# ESP32_RF.net
KiCad netlist of a schematic drawn in Altium Designer
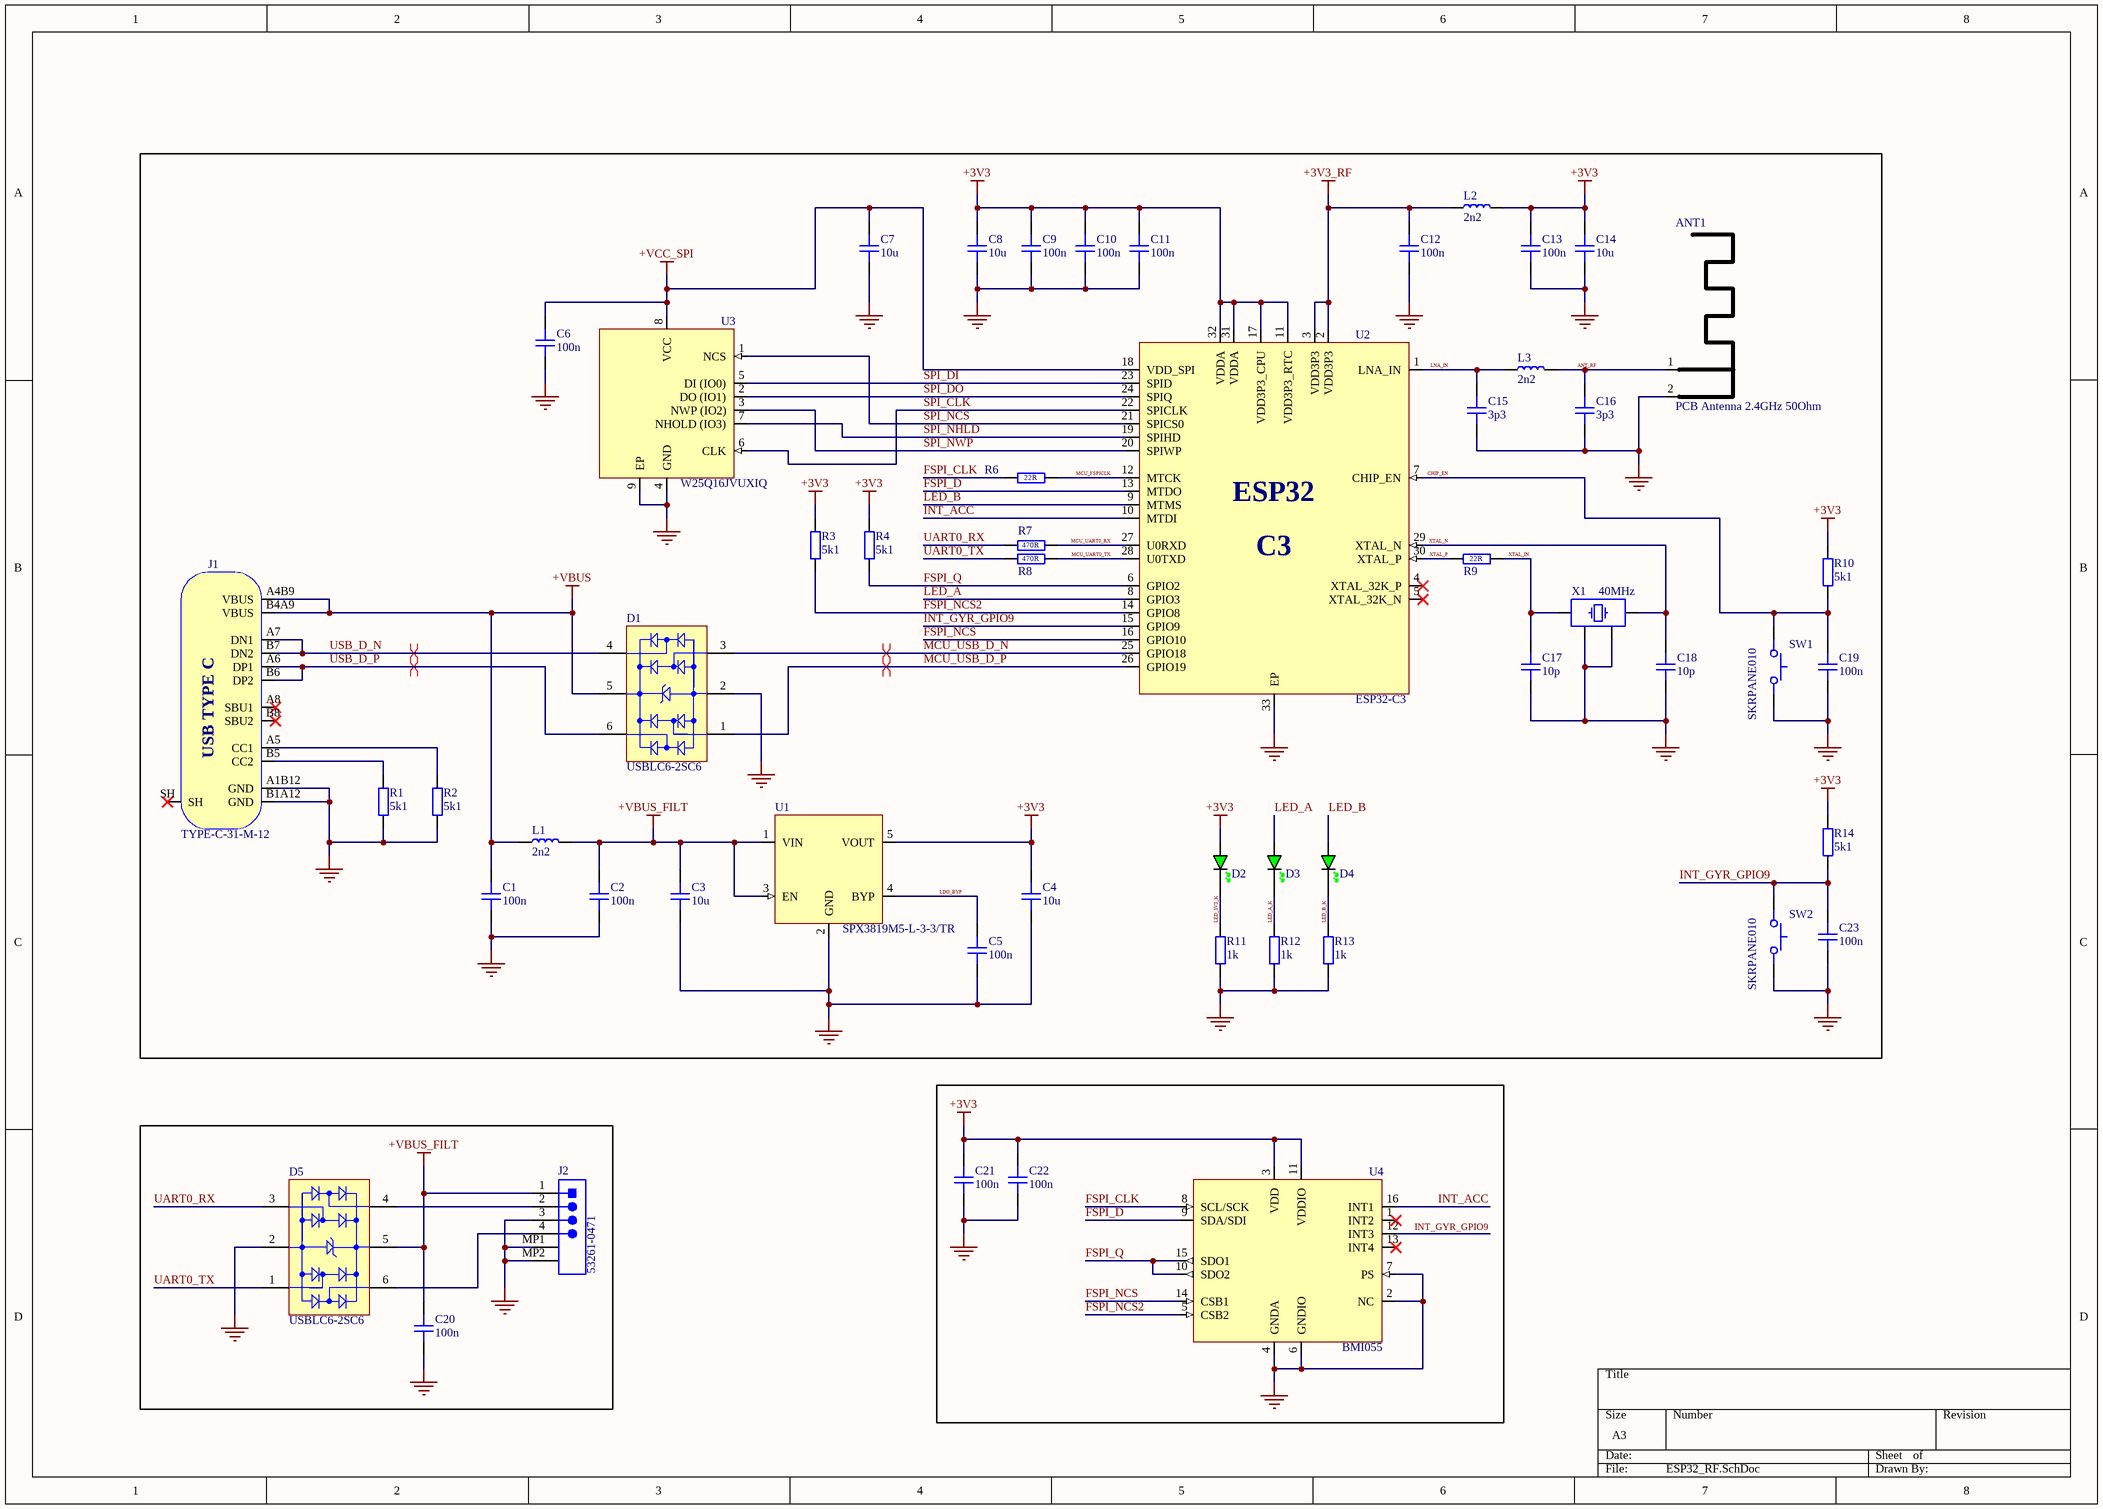
[diagram p0: ESP32_RF.SchDoc]

(export (version "E")
  (design (tool "Eeschema 10.0.6"))
  (components
    (comp (ref "ANT1")
      (value "PCB Antenna 2.4GHz 50Ohm")
      (footprint "ANT_IFA_USB_2_4GHZ_50R")
      (description "Inverted F 2.4GHz ISM PCB Antenna 50 Ohm")
      (libsource (lib "Schematic-Lib-PhilsLab") (part "ANT_IFA_USB_2_4GHZ_50R"))
    )
    (comp (ref "C1")
      (value "100n")
      (footprint "CAP_0402")
      (description "Capacitor SMD 0402 50V")
      (fields
        (field (name "MANUFACTURER") "Samsung")
        (field (name "MANUFACTURER PART NUMBER") "CL05B104KO5NNNC")
      )
      (libsource (lib "Schematic-Lib-PhilsLab") (part "CAP_0402_50V"))
    )
    (comp (ref "C2")
      (value "100n")
      (footprint "CAP_0402")
      (description "Capacitor SMD 0402 50V")
      (fields
        (field (name "MANUFACTURER") "Samsung")
        (field (name "MANUFACTURER PART NUMBER") "CL05B104KO5NNNC")
      )
      (libsource (lib "Schematic-Lib-PhilsLab") (part "CAP_0402_50V"))
    )
    (comp (ref "C3")
      (value "10u")
      (footprint "CAP_0603")
      (description "Capacitor SMD 0603 10V")
      (fields
        (field (name "MANUFACTURER") "Samsung")
        (field (name "MANUFACTURER PART NUMBER") "CL10A106KP8NNNC")
      )
      (libsource (lib "Schematic-Lib-PhilsLab") (part "CAP_0603_10V"))
    )
    (comp (ref "C4")
      (value "10u")
      (footprint "CAP_0603")
      (description "Capacitor SMD 0603 10V")
      (fields
        (field (name "MANUFACTURER") "Samsung")
        (field (name "MANUFACTURER PART NUMBER") "CL10A106KP8NNNC")
      )
      (libsource (lib "Schematic-Lib-PhilsLab") (part "CAP_0603_10V"))
    )
    (comp (ref "C5")
      (value "100n")
      (footprint "CAP_0402")
      (description "Capacitor SMD 0402 50V")
      (fields
        (field (name "MANUFACTURER") "Samsung")
        (field (name "MANUFACTURER PART NUMBER") "CL05B104KO5NNNC")
      )
      (libsource (lib "Schematic-Lib-PhilsLab") (part "CAP_0402_50V"))
    )
    (comp (ref "C6")
      (value "100n")
      (footprint "CAP_0402")
      (description "Capacitor SMD 0402 50V")
      (fields
        (field (name "MANUFACTURER") "Samsung")
        (field (name "MANUFACTURER PART NUMBER") "CL05B104KO5NNNC")
      )
      (libsource (lib "Schematic-Lib-PhilsLab") (part "CAP_0402_50V"))
    )
    (comp (ref "C7")
      (value "10u")
      (footprint "CAP_0603")
      (description "Capacitor SMD 0603 10V")
      (fields
        (field (name "MANUFACTURER") "Samsung")
        (field (name "MANUFACTURER PART NUMBER") "CL10A106KP8NNNC")
      )
      (libsource (lib "Schematic-Lib-PhilsLab") (part "CAP_0603_10V"))
    )
    (comp (ref "C8")
      (value "10u")
      (footprint "CAP_0603")
      (description "Capacitor SMD 0603 10V")
      (fields
        (field (name "MANUFACTURER") "Samsung")
        (field (name "MANUFACTURER PART NUMBER") "CL10A106KP8NNNC")
      )
      (libsource (lib "Schematic-Lib-PhilsLab") (part "CAP_0603_10V"))
    )
    (comp (ref "C9")
      (value "100n")
      (footprint "CAP_0402")
      (description "Capacitor SMD 0402 50V")
      (fields
        (field (name "MANUFACTURER") "Samsung")
        (field (name "MANUFACTURER PART NUMBER") "CL05B104KO5NNNC")
      )
      (libsource (lib "Schematic-Lib-PhilsLab") (part "CAP_0402_50V"))
    )
    (comp (ref "C10")
      (value "100n")
      (footprint "CAP_0402")
      (description "Capacitor SMD 0402 50V")
      (fields
        (field (name "MANUFACTURER") "Samsung")
        (field (name "MANUFACTURER PART NUMBER") "CL05B104KO5NNNC")
      )
      (libsource (lib "Schematic-Lib-PhilsLab") (part "CAP_0402_50V"))
    )
    (comp (ref "C11")
      (value "100n")
      (footprint "CAP_0402")
      (description "Capacitor SMD 0402 50V")
      (fields
        (field (name "MANUFACTURER") "Samsung")
        (field (name "MANUFACTURER PART NUMBER") "CL05B104KO5NNNC")
      )
      (libsource (lib "Schematic-Lib-PhilsLab") (part "CAP_0402_50V"))
    )
    (comp (ref "C12")
      (value "100n")
      (footprint "CAP_0402")
      (description "Capacitor SMD 0402 50V")
      (fields
        (field (name "MANUFACTURER") "Samsung")
        (field (name "MANUFACTURER PART NUMBER") "CL05B104KO5NNNC")
      )
      (libsource (lib "Schematic-Lib-PhilsLab") (part "CAP_0402_50V"))
    )
    (comp (ref "C13")
      (value "100n")
      (footprint "CAP_0402")
      (description "Capacitor SMD 0402 50V")
      (fields
        (field (name "MANUFACTURER") "Samsung")
        (field (name "MANUFACTURER PART NUMBER") "CL05B104KO5NNNC")
      )
      (libsource (lib "Schematic-Lib-PhilsLab") (part "CAP_0402_50V"))
    )
    (comp (ref "C14")
      (value "10u")
      (footprint "CAP_0603")
      (description "Capacitor SMD 0603 10V")
      (fields
        (field (name "MANUFACTURER") "Samsung")
        (field (name "MANUFACTURER PART NUMBER") "CL10A106KP8NNNC")
      )
      (libsource (lib "Schematic-Lib-PhilsLab") (part "CAP_0603_10V"))
    )
    (comp (ref "C15")
      (value "3p3")
      (footprint "CAP_0402")
      (description "Capacitor SMD 0402 50V")
      (fields (field (name "MANUFACTURER") "FH") (field (name "MANUFACTURER PART NUMBER") "0402CG3R3C500NT"))
      (libsource (lib "Schematic-Lib-PhilsLab") (part "CAP_0402_50V"))
    )
    (comp (ref "C16")
      (value "3p3")
      (footprint "CAP_0402")
      (description "Capacitor SMD 0402 50V")
      (fields (field (name "MANUFACTURER") "FH") (field (name "MANUFACTURER PART NUMBER") "0402CG3R3C500NT"))
      (libsource (lib "Schematic-Lib-PhilsLab") (part "CAP_0402_50V"))
    )
    (comp (ref "C17")
      (value "10p")
      (footprint "CAP_0402")
      (description "Capacitor SMD 0402 50V")
      (fields
        (field (name "MANUFACTURER") "Samsung")
        (field (name "MANUFACTURER PART NUMBER") "CL05C100JB5NNNC")
      )
      (libsource (lib "Schematic-Lib-PhilsLab") (part "CAP_0402_50V"))
    )
    (comp (ref "C18")
      (value "10p")
      (footprint "CAP_0402")
      (description "Capacitor SMD 0402 50V")
      (fields
        (field (name "MANUFACTURER") "Samsung")
        (field (name "MANUFACTURER PART NUMBER") "CL05C100JB5NNNC")
      )
      (libsource (lib "Schematic-Lib-PhilsLab") (part "CAP_0402_50V"))
    )
    (comp (ref "C19")
      (value "100n")
      (footprint "CAP_0402")
      (description "Capacitor SMD 0402 50V")
      (fields
        (field (name "MANUFACTURER") "Samsung")
        (field (name "MANUFACTURER PART NUMBER") "CL05B104KO5NNNC")
      )
      (libsource (lib "Schematic-Lib-PhilsLab") (part "CAP_0402_50V"))
    )
    (comp (ref "C20")
      (value "100n")
      (footprint "CAP_0402")
      (description "Capacitor SMD 0402 50V")
      (fields
        (field (name "MANUFACTURER") "Samsung")
        (field (name "MANUFACTURER PART NUMBER") "CL05B104KO5NNNC")
      )
      (libsource (lib "Schematic-Lib-PhilsLab") (part "CAP_0402_50V"))
    )
    (comp (ref "C21")
      (value "100n")
      (footprint "CAP_0402")
      (description "Capacitor SMD 0402 50V")
      (fields
        (field (name "MANUFACTURER") "Samsung")
        (field (name "MANUFACTURER PART NUMBER") "CL05B104KO5NNNC")
      )
      (libsource (lib "Schematic-Lib-PhilsLab") (part "CAP_0402_50V"))
    )
    (comp (ref "C22")
      (value "100n")
      (footprint "CAP_0402")
      (description "Capacitor SMD 0402 50V")
      (fields
        (field (name "MANUFACTURER") "Samsung")
        (field (name "MANUFACTURER PART NUMBER") "CL05B104KO5NNNC")
      )
      (libsource (lib "Schematic-Lib-PhilsLab") (part "CAP_0402_50V"))
    )
    (comp (ref "C23")
      (value "100n")
      (footprint "CAP_0402")
      (description "Capacitor SMD 0402 50V")
      (fields
        (field (name "MANUFACTURER") "Samsung")
        (field (name "MANUFACTURER PART NUMBER") "CL05B104KO5NNNC")
      )
      (libsource (lib "Schematic-Lib-PhilsLab") (part "CAP_0402_50V"))
    )
    (comp (ref "D1")
      (value "USBLC6-2SC6")
      (footprint "STM-SOT23-6L_V")
      (description "Very low capacitance ESD protection, 3.5 pF, -40 to 125 degC, 6-Pin SOT23, RoHS, Tape and Reel")
      (fields (field (name "MANUFACTURER") "STMicroelectronics"))
      (libsource (lib "Altium Content Vault") (part "STM-USB_DVI_HDMIULC6-4SC6X-SOT23-6L"))
    )
    (comp (ref "D2")
      (value "GREEN")
      (footprint "LED_0603_GREEN")
      (description "LED 0603 GREEN SMD")
      (libsource (lib "Schematic-Lib-PhilsLab") (part "LED_0603_GREEN"))
    )
    (comp (ref "D3")
      (value "GREEN")
      (footprint "LED_0603_GREEN")
      (description "LED 0603 GREEN SMD")
      (libsource (lib "Schematic-Lib-PhilsLab") (part "LED_0603_GREEN"))
    )
    (comp (ref "D4")
      (value "GREEN")
      (footprint "LED_0603_GREEN")
      (description "LED 0603 GREEN SMD")
      (libsource (lib "Schematic-Lib-PhilsLab") (part "LED_0603_GREEN"))
    )
    (comp (ref "D5")
      (value "USBLC6-2SC6")
      (footprint "STM-SOT23-6L_V")
      (description "Very low capacitance ESD protection, 3.5 pF, -40 to 125 degC, 6-Pin SOT23, RoHS, Tape and Reel")
      (fields (field (name "MANUFACTURER") "STMicroelectronics"))
      (libsource (lib "Altium Content Vault") (part "STM-USB_DVI_HDMIULC6-4SC6X-SOT23-6L"))
    )
    (comp (ref "J1")
      (value "TYPE-C-31-M-12")
      (footprint "TYPE-C-31-M-12")
      (description "USB Type C Connector Horizontal SMT")
      (fields (field (name "MANUFACTURER") "Koren Hroparts"))
      (libsource (lib "Schematic-Lib-PhilsLab") (part "TYPE-C-31-M-12"))
    )
    (comp (ref "J2")
      (value "53261-0471")
      (footprint "MOLEX-53261-0471_V")
      (description "Male Header, Pitch 1.25 mm, 1 x 4 Position, Height 3.4 mm, -40 to 85 degC, RoHS, Tape and Reel")
      (fields (field (name "MANUFACTURER") "Molex"))
      (libsource (lib "Altium Content Vault") (part "CN-1P-2M-R4_A"))
    )
    (comp (ref "L1")
      (value "2n2")
      (footprint "IND_0402")
      (description "Inductor SMD 0402")
      (fields
        (field (name "MANUFACTURER") "Murata")
        (field (name "MANUFACTURER PART NUMBER") "LQW15AN2N2G80D")
      )
      (libsource (lib "Schematic-Lib-PhilsLab") (part "IND_0402"))
    )
    (comp (ref "L2")
      (value "2n2")
      (footprint "IND_0402")
      (description "Inductor SMD 0402")
      (fields
        (field (name "MANUFACTURER") "Murata")
        (field (name "MANUFACTURER PART NUMBER") "LQW15AN2N2G80D")
      )
      (libsource (lib "Schematic-Lib-PhilsLab") (part "IND_0402"))
    )
    (comp (ref "L3")
      (value "2n2")
      (footprint "IND_0402")
      (description "Inductor SMD 0402")
      (fields
        (field (name "MANUFACTURER") "Murata")
        (field (name "MANUFACTURER PART NUMBER") "LQW15AN2N2G80D")
      )
      (libsource (lib "Schematic-Lib-PhilsLab") (part "IND_0402"))
    )
    (comp (ref "R1")
      (value "5k1")
      (footprint "RES_0402")
      (description "Resistor SMD 0402")
      (fields
        (field (name "MANUFACTURER") "YAGEO")
        (field (name "MANUFACTURER PART NUMBER") "RC0402JR-075K1L")
      )
      (libsource (lib "Schematic-Lib-PhilsLab") (part "RES_0402"))
    )
    (comp (ref "R2")
      (value "5k1")
      (footprint "RES_0402")
      (description "Resistor SMD 0402")
      (fields
        (field (name "MANUFACTURER") "YAGEO")
        (field (name "MANUFACTURER PART NUMBER") "RC0402JR-075K1L")
      )
      (libsource (lib "Schematic-Lib-PhilsLab") (part "RES_0402"))
    )
    (comp (ref "R3")
      (value "5k1")
      (footprint "RES_0402")
      (description "Resistor SMD 0402")
      (fields
        (field (name "MANUFACTURER") "YAGEO")
        (field (name "MANUFACTURER PART NUMBER") "RC0402JR-075K1L")
      )
      (libsource (lib "Schematic-Lib-PhilsLab") (part "RES_0402"))
    )
    (comp (ref "R4")
      (value "5k1")
      (footprint "RES_0402")
      (description "Resistor SMD 0402")
      (fields
        (field (name "MANUFACTURER") "YAGEO")
        (field (name "MANUFACTURER PART NUMBER") "RC0402JR-075K1L")
      )
      (libsource (lib "Schematic-Lib-PhilsLab") (part "RES_0402"))
    )
    (comp (ref "R6")
      (value "22R")
      (footprint "RES_0402")
      (description "Resistor SMD 0402")
      (fields
        (field (name "MANUFACTURER") "UNI-ROYAL")
        (field (name "MANUFACTURER PART NUMBER") "0402WGF220JTCE")
      )
      (libsource (lib "Schematic-Lib-PhilsLab") (part "RES_0402"))
    )
    (comp (ref "R7")
      (value "470R")
      (footprint "RES_0402")
      (description "Resistor SMD 0402")
      (fields
        (field (name "MANUFACTURER") "UNI-ROYAL")
        (field (name "MANUFACTURER PART NUMBER") "0402WGF4700TCE")
      )
      (libsource (lib "Schematic-Lib-PhilsLab") (part "RES_0402"))
    )
    (comp (ref "R8")
      (value "470R")
      (footprint "RES_0402")
      (description "Resistor SMD 0402")
      (fields
        (field (name "MANUFACTURER") "UNI-ROYAL")
        (field (name "MANUFACTURER PART NUMBER") "0402WGF4700TCE")
      )
      (libsource (lib "Schematic-Lib-PhilsLab") (part "RES_0402"))
    )
    (comp (ref "R9")
      (value "22R")
      (footprint "RES_0402")
      (description "Resistor SMD 0402")
      (fields
        (field (name "MANUFACTURER") "UNI-ROYAL")
        (field (name "MANUFACTURER PART NUMBER") "0402WGF220JTCE")
      )
      (libsource (lib "Schematic-Lib-PhilsLab") (part "RES_0402"))
    )
    (comp (ref "R10")
      (value "5k1")
      (footprint "RES_0402")
      (description "Resistor SMD 0402")
      (fields
        (field (name "MANUFACTURER") "YAGEO")
        (field (name "MANUFACTURER PART NUMBER") "RC0402JR-075K1L")
      )
      (libsource (lib "Schematic-Lib-PhilsLab") (part "RES_0402"))
    )
    (comp (ref "R11")
      (value "1k")
      (footprint "RES_0402")
      (description "Resistor SMD 0402")
      (fields
        (field (name "MANUFACTURER") "UNI-ROYAL")
        (field (name "MANUFACTURER PART NUMBER") "0402WGF4700TCE")
      )
      (libsource (lib "Schematic-Lib-PhilsLab") (part "RES_0402"))
    )
    (comp (ref "R12")
      (value "1k")
      (footprint "RES_0402")
      (description "Resistor SMD 0402")
      (fields
        (field (name "MANUFACTURER") "UNI-ROYAL")
        (field (name "MANUFACTURER PART NUMBER") "0402WGF4700TCE")
      )
      (libsource (lib "Schematic-Lib-PhilsLab") (part "RES_0402"))
    )
    (comp (ref "R13")
      (value "1k")
      (footprint "RES_0402")
      (description "Resistor SMD 0402")
      (fields
        (field (name "MANUFACTURER") "UNI-ROYAL")
        (field (name "MANUFACTURER PART NUMBER") "0402WGF4700TCE")
      )
      (libsource (lib "Schematic-Lib-PhilsLab") (part "RES_0402"))
    )
    (comp (ref "R14")
      (value "5k1")
      (footprint "RES_0402")
      (description "Resistor SMD 0402")
      (fields
        (field (name "MANUFACTURER") "YAGEO")
        (field (name "MANUFACTURER PART NUMBER") "RC0402JR-075K1L")
      )
      (libsource (lib "Schematic-Lib-PhilsLab") (part "RES_0402"))
    )
    (comp (ref "SW1")
      (value "SKRPANE010")
      (footprint "SKRPANE010")
      (description "Tactile Switch SMD SPST")
      (fields (field (name "MANUFACTURER") "Alps Alpine"))
      (libsource (lib "Schematic-Lib-PhilsLab") (part "SKRPANE010"))
    )
    (comp (ref "SW2")
      (value "SKRPANE010")
      (footprint "SKRPANE010")
      (description "Tactile Switch SMD SPST")
      (fields (field (name "MANUFACTURER") "Alps Alpine"))
      (libsource (lib "Schematic-Lib-PhilsLab") (part "SKRPANE010"))
    )
    (comp (ref "U1")
      (value "SPX3819M5-L-3-3/TR")
      (footprint "SOT-23-5")
      (description "500mA +3.3V Low-Noise LDO Voltage Regulator")
      (fields (field (name "MANUFACTURER") "MaxLinear"))
      (libsource (lib "Schematic-Lib-PhilsLab") (part "SPX3819M5-L-3-3/TR"))
    )
    (comp (ref "U2")
      (value "ESP32-C3")
      (footprint "QFN32-5x5")
      (fields (field (name "MANUFACTURER") "Espressif"))
      (libsource (lib "Schematic-Lib-PhilsLab") (part "ESP32-C3"))
    )
    (comp (ref "U3")
      (value "W25Q16JVUXIQ")
      (footprint "USON-8-2X3MM")
      (description "16M-BIT SERIAL FLASH MEMORY WITH\r\nDUAL/QUAD SPI USON-8")
      (fields (field (name "MANUFACTURER") "Winbond"))
      (libsource (lib "Schematic-Lib-PhilsLab") (part "W25Q16JVUXIQ"))
    )
    (comp (ref "U4")
      (value "BMI055")
      (footprint "BMI088")
      (description "Inertial Measurement Unit IMU 6-Axis LGA")
      (fields (field (name "MANUFACTURER") "Bosch"))
      (libsource (lib "Schematic-Lib-PhilsLab") (part "BMI055"))
    )
    (comp (ref "X1")
      (value "40MHz")
      (footprint "XTAL_2520")
      (description "Crystal SMD 2520")
      (fields (field (name "MANUFACTURER") "Seiko Epson"))
      (libsource (lib "Schematic-Lib-PhilsLab") (part "XTAL_2520"))
    )
  )
  (nets
    (net (code "1") (name "+3V3") (class "Default")
      (node (ref "C10") (pin "2") (pinfunction "2_2") (pintype "passive"))
      (node (ref "C11") (pin "2") (pinfunction "2_2") (pintype "passive"))
      (node (ref "C13") (pin "2") (pinfunction "2_2") (pintype "passive"))
      (node (ref "C14") (pin "2") (pinfunction "2_2") (pintype "passive"))
      (node (ref "C21") (pin "2") (pinfunction "2_2") (pintype "passive"))
      (node (ref "C22") (pin "2") (pinfunction "2_2") (pintype "passive"))
      (node (ref "C4") (pin "2") (pinfunction "2_2") (pintype "passive"))
      (node (ref "C8") (pin "2") (pinfunction "2_2") (pintype "passive"))
      (node (ref "C9") (pin "2") (pinfunction "2_2") (pintype "passive"))
      (node (ref "D2") (pin "A") (pinfunction "A_A") (pintype "passive"))
      (node (ref "L2") (pin "1") (pinfunction "1_1") (pintype "passive"))
      (node (ref "R10") (pin "2") (pinfunction "2_2") (pintype "passive"))
      (node (ref "R14") (pin "2") (pinfunction "2_2") (pintype "passive"))
      (node (ref "R3") (pin "1") (pinfunction "1_1") (pintype "passive"))
      (node (ref "R4") (pin "1") (pinfunction "1_1") (pintype "passive"))
      (node (ref "U1") (pin "5") (pinfunction "VOUT_5") (pintype "power_in"))
      (node (ref "U2") (pin "11") (pinfunction "VDD3P3_RTC_11") (pintype "power_in"))
      (node (ref "U2") (pin "17") (pinfunction "VDD3P3_CPU_17") (pintype "power_in"))
      (node (ref "U2") (pin "31") (pinfunction "VDDA_31") (pintype "power_in"))
      (node (ref "U2") (pin "32") (pinfunction "VDDA_32") (pintype "power_in"))
      (node (ref "U4") (pin "11") (pinfunction "VDDIO_11") (pintype "power_in"))
      (node (ref "U4") (pin "3") (pinfunction "VDD_3") (pintype "power_in"))
    )
    (net (code "2") (name "+3V3_RF") (class "Default")
      (node (ref "C12") (pin "2") (pinfunction "2_2") (pintype "passive"))
      (node (ref "L2") (pin "2") (pinfunction "2_2") (pintype "passive"))
      (node (ref "U2") (pin "2") (pinfunction "VDD3P3_2") (pintype "power_in"))
      (node (ref "U2") (pin "3") (pinfunction "VDD3P3_3") (pintype "power_in"))
    )
    (net (code "3") (name "+VBUS") (class "Default")
      (node (ref "C1") (pin "2") (pinfunction "2_2") (pintype "passive"))
      (node (ref "D1") (pin "5") (pinfunction "VBUS_5") (pintype "passive"))
      (node (ref "J1") (pin "A4B9") (pinfunction "VBUS_A4B9") (pintype "power_in"))
      (node (ref "J1") (pin "B4A9") (pinfunction "VBUS_B4A9") (pintype "power_in"))
      (node (ref "L1") (pin "2") (pinfunction "2_2") (pintype "passive"))
    )
    (net (code "4") (name "+VBUS_FILT") (class "Default")
      (node (ref "C2") (pin "2") (pinfunction "2_2") (pintype "passive"))
      (node (ref "C20") (pin "2") (pinfunction "2_2") (pintype "passive"))
      (node (ref "C3") (pin "2") (pinfunction "2_2") (pintype "passive"))
      (node (ref "D5") (pin "5") (pinfunction "VBUS_5") (pintype "passive"))
      (node (ref "J2") (pin "1") (pinfunction "1_1") (pintype "passive"))
      (node (ref "L1") (pin "1") (pinfunction "1_1") (pintype "passive"))
      (node (ref "U1") (pin "1") (pinfunction "VIN_1") (pintype "power_in"))
      (node (ref "U1") (pin "3") (pinfunction "EN_3") (pintype "input"))
    )
    (net (code "5") (name "+VCC_SPI") (class "Default")
      (node (ref "C6") (pin "2") (pinfunction "2_2") (pintype "passive"))
      (node (ref "C7") (pin "2") (pinfunction "2_2") (pintype "passive"))
      (node (ref "U2") (pin "18") (pinfunction "VDD_SPI_18") (pintype "power_in"))
      (node (ref "U3") (pin "8") (pinfunction "VCC_8") (pintype "power_in"))
    )
    (net (code "6") (name "/ANT_RF") (class "Default")
      (node (ref "ANT1") (pin "1") (pinfunction "RF_1") (pintype "passive"))
      (node (ref "C16") (pin "2") (pinfunction "2_2") (pintype "passive"))
      (node (ref "L3") (pin "1") (pinfunction "1_1") (pintype "passive"))
    )
    (net (code "7") (name "/CHIP_EN") (class "Default")
      (node (ref "C19") (pin "2") (pinfunction "2_2") (pintype "passive"))
      (node (ref "R10") (pin "1") (pinfunction "1_1") (pintype "passive"))
      (node (ref "SW1") (pin "34") (pintype "passive"))
      (node (ref "U2") (pin "7") (pinfunction "CHIP_EN_7") (pintype "input"))
    )
    (net (code "8") (name "/FSPI_CLK") (class "Default")
      (node (ref "R6") (pin "1") (pinfunction "1_1") (pintype "passive"))
      (node (ref "U4") (pin "8") (pinfunction "SCL/SCK_8") (pintype "input"))
    )
    (net (code "9") (name "/FSPI_D") (class "Default")
      (node (ref "U2") (pin "13") (pinfunction "MTDO_13") (pintype "bidirectional"))
      (node (ref "U4") (pin "9") (pinfunction "SDA/SDI_9") (pintype "bidirectional"))
    )
    (net (code "10") (name "/FSPI_NCS") (class "Default")
      (node (ref "U2") (pin "16") (pinfunction "GPIO10_16") (pintype "bidirectional"))
      (node (ref "U4") (pin "14") (pinfunction "CSB1_14") (pintype "input"))
    )
    (net (code "11") (name "/FSPI_NCS2") (class "Default")
      (node (ref "R3") (pin "2") (pinfunction "2_2") (pintype "passive"))
      (node (ref "U2") (pin "14") (pinfunction "GPIO8_14") (pintype "bidirectional"))
      (node (ref "U4") (pin "5") (pinfunction "CSB2_5") (pintype "input"))
    )
    (net (code "12") (name "/FSPI_Q") (class "Default")
      (node (ref "R4") (pin "2") (pinfunction "2_2") (pintype "passive"))
      (node (ref "U2") (pin "6") (pinfunction "GPIO2_6") (pintype "bidirectional"))
      (node (ref "U4") (pin "10") (pinfunction "SDO2_10") (pintype "output"))
      (node (ref "U4") (pin "15") (pinfunction "SDO1_15") (pintype "output"))
    )
    (net (code "13") (name "/INT_ACC") (class "Default")
      (node (ref "U2") (pin "10") (pinfunction "MTDI_10") (pintype "bidirectional"))
      (node (ref "U4") (pin "16") (pinfunction "INT1_16") (pintype "bidirectional"))
    )
    (net (code "14") (name "/INT_GYR_GPIO9") (class "Default")
      (node (ref "C23") (pin "2") (pinfunction "2_2") (pintype "passive"))
      (node (ref "R14") (pin "1") (pinfunction "1_1") (pintype "passive"))
      (node (ref "SW2") (pin "34") (pintype "passive"))
      (node (ref "U2") (pin "15") (pinfunction "GPIO9_15") (pintype "bidirectional"))
      (node (ref "U4") (pin "12") (pinfunction "INT3_12") (pintype "bidirectional"))
    )
    (net (code "15") (name "/LDO_BYP") (class "Default")
      (node (ref "C5") (pin "2") (pinfunction "2_2") (pintype "passive"))
      (node (ref "U1") (pin "4") (pinfunction "BYP_4") (pintype "passive"))
    )
    (net (code "16") (name "/LED_3V3_K") (class "Default")
      (node (ref "D2") (pin "K") (pinfunction "K_K") (pintype "passive"))
      (node (ref "R11") (pin "2") (pinfunction "2_2") (pintype "passive"))
    )
    (net (code "17") (name "/LED_A") (class "Default")
      (node (ref "D3") (pin "A") (pinfunction "A_A") (pintype "passive"))
      (node (ref "U2") (pin "8") (pinfunction "GPIO3_8") (pintype "bidirectional"))
    )
    (net (code "18") (name "/LED_A_K") (class "Default")
      (node (ref "D3") (pin "K") (pinfunction "K_K") (pintype "passive"))
      (node (ref "R12") (pin "2") (pinfunction "2_2") (pintype "passive"))
    )
    (net (code "19") (name "/LED_B") (class "Default")
      (node (ref "D4") (pin "A") (pinfunction "A_A") (pintype "passive"))
      (node (ref "U2") (pin "9") (pinfunction "MTMS_9") (pintype "bidirectional"))
    )
    (net (code "20") (name "/LED_B_K") (class "Default")
      (node (ref "D4") (pin "K") (pinfunction "K_K") (pintype "passive"))
      (node (ref "R13") (pin "2") (pinfunction "2_2") (pintype "passive"))
    )
    (net (code "21") (name "/LNA_IN") (class "Default")
      (node (ref "C15") (pin "2") (pinfunction "2_2") (pintype "passive"))
      (node (ref "L3") (pin "2") (pinfunction "2_2") (pintype "passive"))
      (node (ref "U2") (pin "1") (pinfunction "LNA_IN_1") (pintype "bidirectional"))
    )
    (net (code "22") (name "/MCU_FSPICLK") (class "Default")
      (node (ref "R6") (pin "2") (pinfunction "2_2") (pintype "passive"))
      (node (ref "U2") (pin "12") (pinfunction "MTCK_12") (pintype "bidirectional"))
    )
    (net (code "23") (name "/MCU_UART0_RX") (class "Default")
      (node (ref "R7") (pin "2") (pinfunction "2_2") (pintype "passive"))
      (node (ref "U2") (pin "27") (pinfunction "U0RXD_27") (pintype "bidirectional"))
    )
    (net (code "24") (name "/MCU_UART0_TX") (class "Default")
      (node (ref "R8") (pin "2") (pinfunction "2_2") (pintype "passive"))
      (node (ref "U2") (pin "28") (pinfunction "U0TXD_28") (pintype "bidirectional"))
    )
    (net (code "25") (name "/MCU_USB_D_N") (class "Default")
      (node (ref "D1") (pin "3") (pinfunction "I/O_2_3") (pintype "passive"))
      (node (ref "U2") (pin "25") (pinfunction "GPIO18_25") (pintype "bidirectional"))
    )
    (net (code "26") (name "/MCU_USB_D_P") (class "Default")
      (node (ref "D1") (pin "1") (pinfunction "I/O_1_1") (pintype "passive"))
      (node (ref "U2") (pin "26") (pinfunction "GPIO19_26") (pintype "bidirectional"))
    )
    (net (code "27") (name "/SPI_CLK") (class "Default")
      (node (ref "U2") (pin "22") (pinfunction "SPICLK_22") (pintype "bidirectional"))
      (node (ref "U3") (pin "6") (pinfunction "CLK_6") (pintype "input"))
    )
    (net (code "28") (name "/SPI_DI") (class "Default")
      (node (ref "U2") (pin "23") (pinfunction "SPID_23") (pintype "bidirectional"))
      (node (ref "U3") (pin "5") (pinfunction "DI_(IO0)_5") (pintype "bidirectional"))
    )
    (net (code "29") (name "/SPI_DO") (class "Default")
      (node (ref "U2") (pin "24") (pinfunction "SPIQ_24") (pintype "bidirectional"))
      (node (ref "U3") (pin "2") (pinfunction "DO_(IO1)_2") (pintype "bidirectional"))
    )
    (net (code "30") (name "/SPI_NCS") (class "Default")
      (node (ref "U2") (pin "21") (pinfunction "SPICS0_21") (pintype "bidirectional"))
      (node (ref "U3") (pin "1") (pinfunction "NCS_1") (pintype "input"))
    )
    (net (code "31") (name "/SPI_NHLD") (class "Default")
      (node (ref "U2") (pin "19") (pinfunction "SPIHD_19") (pintype "bidirectional"))
      (node (ref "U3") (pin "7") (pinfunction "NHOLD_(IO3)_7") (pintype "bidirectional"))
    )
    (net (code "32") (name "/SPI_NWP") (class "Default")
      (node (ref "U2") (pin "20") (pinfunction "SPIWP_20") (pintype "bidirectional"))
      (node (ref "U3") (pin "3") (pinfunction "NWP_(IO2)_3") (pintype "bidirectional"))
    )
    (net (code "33") (name "/UART0_RX") (class "Default")
      (node (ref "D5") (pin "3") (pinfunction "I/O_2_3") (pintype "passive"))
      (node (ref "R7") (pin "1") (pinfunction "1_1") (pintype "passive"))
    )
    (net (code "34") (name "/UART0_TX") (class "Default")
      (node (ref "D5") (pin "1") (pinfunction "I/O_1_1") (pintype "passive"))
      (node (ref "R8") (pin "1") (pinfunction "1_1") (pintype "passive"))
    )
    (net (code "35") (name "/USB_D_N") (class "Default")
      (node (ref "D1") (pin "4") (pinfunction "I/O_3_4") (pintype "passive"))
      (node (ref "J1") (pin "A7") (pinfunction "DN1_A7") (pintype "bidirectional"))
      (node (ref "J1") (pin "B7") (pinfunction "DN2_B7") (pintype "bidirectional"))
    )
    (net (code "36") (name "/USB_D_P") (class "Default")
      (node (ref "D1") (pin "6") (pinfunction "I/O_4_6") (pintype "passive"))
      (node (ref "J1") (pin "A6") (pinfunction "DP1_A6") (pintype "bidirectional"))
      (node (ref "J1") (pin "B6") (pinfunction "DP2_B6") (pintype "bidirectional"))
    )
    (net (code "37") (name "/XTAL_IN") (class "Default")
      (node (ref "C17") (pin "2") (pinfunction "2_2") (pintype "passive"))
      (node (ref "R9") (pin "2") (pinfunction "2_2") (pintype "passive"))
      (node (ref "X1") (pin "3") (pinfunction "3_3") (pintype "passive"))
    )
    (net (code "38") (name "/XTAL_N") (class "Default")
      (node (ref "C18") (pin "2") (pinfunction "2_2") (pintype "passive"))
      (node (ref "U2") (pin "29") (pinfunction "XTAL_N_29") (pintype "input"))
      (node (ref "X1") (pin "1") (pinfunction "1_1") (pintype "passive"))
    )
    (net (code "39") (name "/XTAL_P") (class "Default")
      (node (ref "R9") (pin "1") (pinfunction "1_1") (pintype "passive"))
      (node (ref "U2") (pin "30") (pinfunction "XTAL_P_30") (pintype "input"))
    )
    (net (code "40") (name "GND") (class "Default")
      (node (ref "ANT1") (pin "2") (pinfunction "GND_2") (pintype "passive"))
      (node (ref "C1") (pin "1") (pinfunction "1_1") (pintype "passive"))
      (node (ref "C10") (pin "1") (pinfunction "1_1") (pintype "passive"))
      (node (ref "C11") (pin "1") (pinfunction "1_1") (pintype "passive"))
      (node (ref "C12") (pin "1") (pinfunction "1_1") (pintype "passive"))
      (node (ref "C13") (pin "1") (pinfunction "1_1") (pintype "passive"))
      (node (ref "C14") (pin "1") (pinfunction "1_1") (pintype "passive"))
      (node (ref "C15") (pin "1") (pinfunction "1_1") (pintype "passive"))
      (node (ref "C16") (pin "1") (pinfunction "1_1") (pintype "passive"))
      (node (ref "C17") (pin "1") (pinfunction "1_1") (pintype "passive"))
      (node (ref "C18") (pin "1") (pinfunction "1_1") (pintype "passive"))
      (node (ref "C19") (pin "1") (pinfunction "1_1") (pintype "passive"))
      (node (ref "C2") (pin "1") (pinfunction "1_1") (pintype "passive"))
      (node (ref "C20") (pin "1") (pinfunction "1_1") (pintype "passive"))
      (node (ref "C21") (pin "1") (pinfunction "1_1") (pintype "passive"))
      (node (ref "C22") (pin "1") (pinfunction "1_1") (pintype "passive"))
      (node (ref "C23") (pin "1") (pinfunction "1_1") (pintype "passive"))
      (node (ref "C3") (pin "1") (pinfunction "1_1") (pintype "passive"))
      (node (ref "C4") (pin "1") (pinfunction "1_1") (pintype "passive"))
      (node (ref "C5") (pin "1") (pinfunction "1_1") (pintype "passive"))
      (node (ref "C6") (pin "1") (pinfunction "1_1") (pintype "passive"))
      (node (ref "C7") (pin "1") (pinfunction "1_1") (pintype "passive"))
      (node (ref "C8") (pin "1") (pinfunction "1_1") (pintype "passive"))
      (node (ref "C9") (pin "1") (pinfunction "1_1") (pintype "passive"))
      (node (ref "D1") (pin "2") (pinfunction "GND_2") (pintype "passive"))
      (node (ref "D5") (pin "2") (pinfunction "GND_2") (pintype "passive"))
      (node (ref "J1") (pin "A1B12") (pinfunction "GND_A1B12") (pintype "power_in"))
      (node (ref "J1") (pin "B1A12") (pinfunction "GND_B1A12") (pintype "power_in"))
      (node (ref "J2") (pin "3") (pinfunction "3_3") (pintype "passive"))
      (node (ref "J2") (pin "MP1") (pinfunction "MP1_MP1") (pintype "passive"))
      (node (ref "J2") (pin "MP2") (pinfunction "MP2_MP2") (pintype "passive"))
      (node (ref "R1") (pin "2") (pinfunction "2_2") (pintype "passive"))
      (node (ref "R11") (pin "1") (pinfunction "1_1") (pintype "passive"))
      (node (ref "R12") (pin "1") (pinfunction "1_1") (pintype "passive"))
      (node (ref "R13") (pin "1") (pinfunction "1_1") (pintype "passive"))
      (node (ref "R2") (pin "2") (pinfunction "2_2") (pintype "passive"))
      (node (ref "SW1") (pin "12") (pintype "passive"))
      (node (ref "SW2") (pin "12") (pintype "passive"))
      (node (ref "U1") (pin "2") (pinfunction "GND_2") (pintype "power_in"))
      (node (ref "U2") (pin "33") (pinfunction "EP_33") (pintype "power_in"))
      (node (ref "U3") (pin "4") (pinfunction "GND_4") (pintype "power_in"))
      (node (ref "U3") (pin "9") (pinfunction "EP_9") (pintype "power_in"))
      (node (ref "U4") (pin "2") (pinfunction "NC_2") (pintype "passive"))
      (node (ref "U4") (pin "4") (pinfunction "GNDA_4") (pintype "power_in"))
      (node (ref "U4") (pin "6") (pinfunction "GNDIO_6") (pintype "power_in"))
      (node (ref "U4") (pin "7") (pinfunction "PS_7") (pintype "input"))
      (node (ref "X1") (pin "2") (pinfunction "2_2") (pintype "passive"))
      (node (ref "X1") (pin "4") (pinfunction "4_4") (pintype "passive"))
    )
    (net (code "41") (name "Net-(D5-I{slash}O_3)") (class "Default")
      (node (ref "D5") (pin "4") (pinfunction "I/O_3_4") (pintype "passive"))
      (node (ref "J2") (pin "2") (pinfunction "2_2") (pintype "passive"))
    )
    (net (code "42") (name "Net-(D5-I{slash}O_4)") (class "Default")
      (node (ref "D5") (pin "6") (pinfunction "I/O_4_6") (pintype "passive"))
      (node (ref "J2") (pin "4") (pinfunction "4_4") (pintype "passive"))
    )
    (net (code "43") (name "Net-(J1-CC1)") (class "Default")
      (node (ref "J1") (pin "A5") (pinfunction "CC1_A5") (pintype "passive"))
      (node (ref "R2") (pin "1") (pinfunction "1_1") (pintype "passive"))
    )
    (net (code "44") (name "Net-(J1-CC2)") (class "Default")
      (node (ref "J1") (pin "B5") (pinfunction "CC2_B5") (pintype "tri_state"))
      (node (ref "R1") (pin "1") (pinfunction "1_1") (pintype "passive"))
    )
    (net (code "45") (name "unconnected-(J1-PadSH)") (class "Default")
      (node (ref "J1") (pin "SH") (pinfunction "SH_SH") (pintype "power_in+no_connect"))
    )
    (net (code "46") (name "unconnected-(J1-SBU1-PadA8)") (class "Default")
      (node (ref "J1") (pin "A8") (pinfunction "SBU1_A8") (pintype "bidirectional+no_connect"))
    )
    (net (code "47") (name "unconnected-(J1-SBU2-PadB8)") (class "Default")
      (node (ref "J1") (pin "B8") (pinfunction "SBU2_B8") (pintype "bidirectional+no_connect"))
    )
    (net (code "48") (name "unconnected-(U2-XTAL_32K_N-Pad5)") (class "Default")
      (node (ref "U2") (pin "5") (pinfunction "XTAL_32K_N_5") (pintype "bidirectional+no_connect"))
    )
    (net (code "49") (name "unconnected-(U2-XTAL_32K_P-Pad4)") (class "Default")
      (node (ref "U2") (pin "4") (pinfunction "XTAL_32K_P_4") (pintype "bidirectional+no_connect"))
    )
    (net (code "50") (name "unconnected-(U4-INT2-Pad1)") (class "Default")
      (node (ref "U4") (pin "1") (pinfunction "INT2_1") (pintype "bidirectional+no_connect"))
    )
    (net (code "51") (name "unconnected-(U4-INT4-Pad13)") (class "Default")
      (node (ref "U4") (pin "13") (pinfunction "INT4_13") (pintype "bidirectional+no_connect"))
    )
  )
)
